# ESP32_Alarm.net
KiCad netlist of a schematic drawn in EAGLE
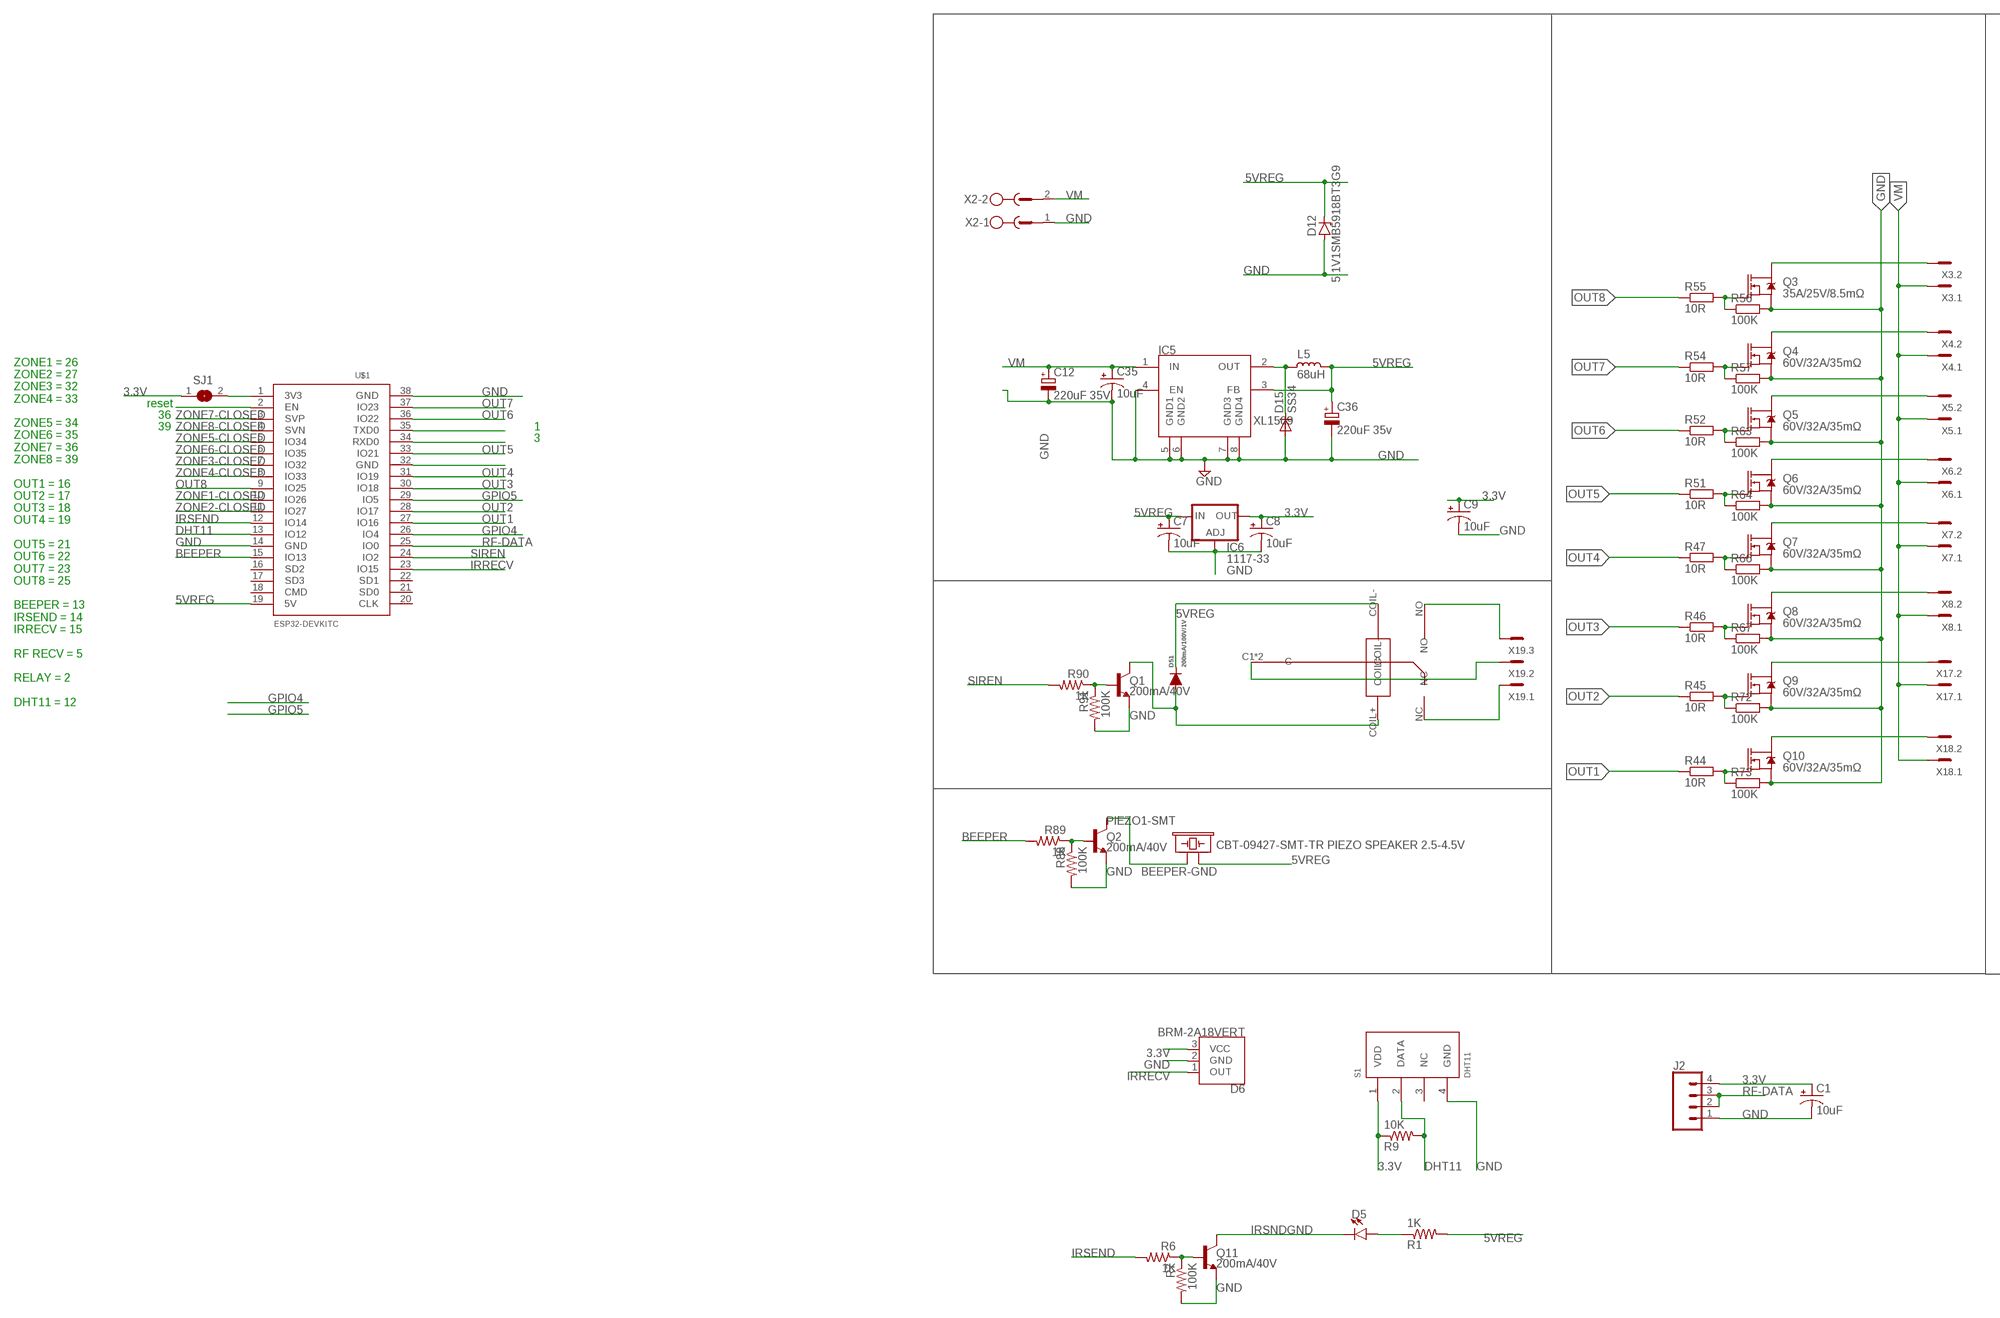
[diagram p0: schematic, sheet 1, part 1 of 2]
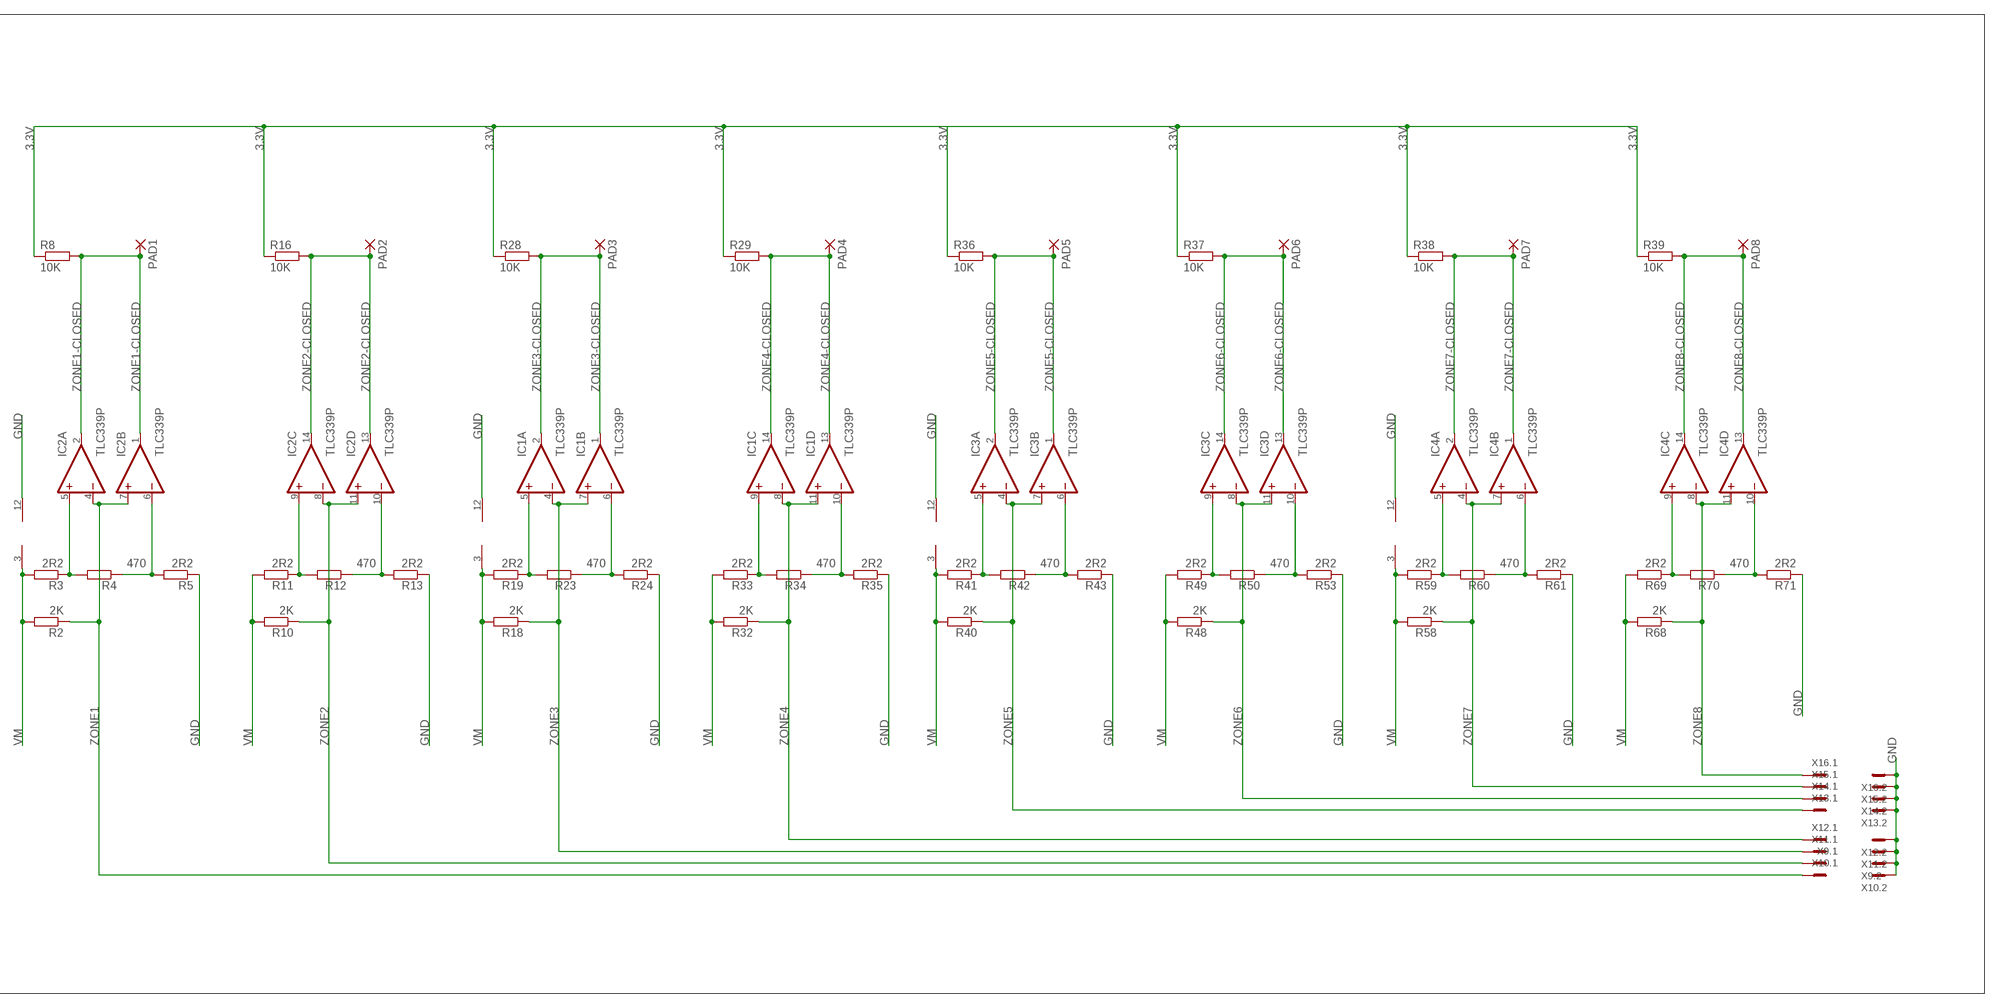
[diagram p1: schematic, sheet 1, part 2 of 2]

(export (version "E")
  (design (tool "Eeschema 10.0.6"))
  (components
    (comp (ref "C1")
      (value "10uF")
      (footprint "eagle-import:EIA3216")
      (libsource (lib "eagle-import") (part "CAP_POL1206"))
    )
    (comp (ref "C7")
      (value "10uF")
      (footprint "eagle-import:EIA3216")
      (libsource (lib "eagle-import") (part "CAP_POL1206"))
    )
    (comp (ref "C8")
      (value "10uF")
      (footprint "eagle-import:EIA3216")
      (libsource (lib "eagle-import") (part "CAP_POL1206"))
    )
    (comp (ref "C9")
      (value "10uF")
      (footprint "eagle-import:EIA3216")
      (libsource (lib "eagle-import") (part "CAP_POL1206"))
    )
    (comp (ref "C12")
      (value "220uF 35V")
      (footprint "eagle-import:E3,5-8")
      (libsource (lib "eagle-import") (part "CPOL-EUE3.5-8"))
    )
    (comp (ref "C35")
      (value "10uF")
      (footprint "eagle-import:EIA3216")
      (libsource (lib "eagle-import") (part "CAP_POL1206"))
    )
    (comp (ref "C36")
      (value "220uF 35v")
      (footprint "eagle-import:E3,5-8")
      (libsource (lib "eagle-import") (part "CPOL-EUE3.5-8"))
    )
    (comp (ref "D5")
      (value "LED3MM")
      (footprint "eagle-import:LED_3MM")
      (libsource (lib "eagle-import") (part "LED3MM"))
    )
    (comp (ref "D6")
      (value "BRM-2A18VERT")
      (footprint "eagle-import:BRM-2508_VERT")
      (libsource (lib "eagle-import") (part "BRM-2A18VERT"))
    )
    (comp (ref "D12")
      (value "5.1V1SMB5918BT3G9")
      (footprint "eagle-import:SMB")
      (libsource (lib "eagle-import") (part "ZENER-DIODESMB"))
    )
    (comp (ref "D15")
      (value "SS34")
      (footprint "eagle-import:DO-214AC")
      (libsource (lib "eagle-import") (part "DIODE-DO-214AC"))
    )
    (comp (ref "D51")
      (value "200mA/100V/1V")
      (footprint "eagle-import:DIODE-1N4148-KIT")
      (libsource (lib "eagle-import") (part "DIODE-KIT"))
    )
    (comp (ref "IC1")
      (value "TLC339P")
      (footprint "eagle-import:DIL14")
      (libsource (lib "eagle-import") (part "TLC339P"))
    )
    (comp (ref "IC2")
      (value "TLC339P")
      (footprint "eagle-import:DIL14")
      (libsource (lib "eagle-import") (part "TLC339P"))
    )
    (comp (ref "IC3")
      (value "TLC339P")
      (footprint "eagle-import:DIL14")
      (libsource (lib "eagle-import") (part "TLC339P"))
    )
    (comp (ref "IC4")
      (value "TLC339P")
      (footprint "eagle-import:DIL14")
      (libsource (lib "eagle-import") (part "TLC339P"))
    )
    (comp (ref "IC5")
      (value "XL1509")
      (footprint "eagle-import:SO08")
      (libsource (lib "eagle-import") (part "XL1509"))
    )
    (comp (ref "IC6")
      (value "1117-33")
      (footprint "eagle-import:SOT223")
      (libsource (lib "eagle-import") (part "LD117A?S33TR"))
    )
    (comp (ref "J1")
      (value "JRC-21F-4100")
      (footprint "eagle-import:JRC-21F-4100")
      (libsource (lib "eagle-import") (part "JRC-21F-4100"))
    )
    (comp (ref "J2")
      (value "CONN_04LOCK")
      (footprint "eagle-import:1X04_LOCK")
      (libsource (lib "eagle-import") (part "CONN_04LOCK"))
    )
    (comp (ref "L5")
      (value "68uH")
      (footprint "eagle-import:CD75")
      (libsource (lib "eagle-import") (part "L_CD75"))
    )
    (comp (ref "PAD1")
      (value "2,15/1,0")
      (footprint "eagle-import:2,15_1,0")
      (libsource (lib "eagle-import") (part "2,15/1,0"))
    )
    (comp (ref "PAD2")
      (value "2,15/1,0")
      (footprint "eagle-import:2,15_1,0")
      (libsource (lib "eagle-import") (part "2,15/1,0"))
    )
    (comp (ref "PAD3")
      (value "2,15/1,0")
      (footprint "eagle-import:2,15_1,0")
      (libsource (lib "eagle-import") (part "2,15/1,0"))
    )
    (comp (ref "PAD4")
      (value "2,15/1,0")
      (footprint "eagle-import:2,15_1,0")
      (libsource (lib "eagle-import") (part "2,15/1,0"))
    )
    (comp (ref "PAD5")
      (value "2,15/1,0")
      (footprint "eagle-import:2,15_1,0")
      (libsource (lib "eagle-import") (part "2,15/1,0"))
    )
    (comp (ref "PAD6")
      (value "2,15/1,0")
      (footprint "eagle-import:2,15_1,0")
      (libsource (lib "eagle-import") (part "2,15/1,0"))
    )
    (comp (ref "PAD7")
      (value "2,15/1,0")
      (footprint "eagle-import:2,15_1,0")
      (libsource (lib "eagle-import") (part "2,15/1,0"))
    )
    (comp (ref "PAD8")
      (value "2,15/1,0")
      (footprint "eagle-import:2,15_1,0")
      (libsource (lib "eagle-import") (part "2,15/1,0"))
    )
    (comp (ref "PIEZO1-SMT")
      (value "CBT-09427-SMT-TR PIEZO SPEAKER 2.5-4.5V")
      (footprint "eagle-import:BUZZER-12MM")
      (libsource (lib "eagle-import") (part "BUZZER-PTH"))
    )
    (comp (ref "Q1")
      (value "200mA/40V")
      (footprint "eagle-import:TO-92")
      (libsource (lib "eagle-import") (part "TRANS_NPN-2N3904"))
    )
    (comp (ref "Q2")
      (value "200mA/40V")
      (footprint "eagle-import:TO-92")
      (libsource (lib "eagle-import") (part "TRANS_NPN-2N3904"))
    )
    (comp (ref "Q3")
      (value "35A/25V/8.5mΩ")
      (footprint "eagle-import:DPAK")
      (libsource (lib "eagle-import") (part "MOSFET-NCH-FDD8780"))
    )
    (comp (ref "Q4")
      (value "60V/32A/35mΩ")
      (footprint "eagle-import:TO220V")
      (libsource (lib "eagle-import") (part "MOSFET-NCH-FQP30N06L"))
    )
    (comp (ref "Q5")
      (value "60V/32A/35mΩ")
      (footprint "eagle-import:TO220V")
      (libsource (lib "eagle-import") (part "MOSFET-NCH-FQP30N06L"))
    )
    (comp (ref "Q6")
      (value "60V/32A/35mΩ")
      (footprint "eagle-import:TO220V")
      (libsource (lib "eagle-import") (part "MOSFET-NCH-FQP30N06L"))
    )
    (comp (ref "Q7")
      (value "60V/32A/35mΩ")
      (footprint "eagle-import:TO220V")
      (libsource (lib "eagle-import") (part "MOSFET-NCH-FQP30N06L"))
    )
    (comp (ref "Q8")
      (value "60V/32A/35mΩ")
      (footprint "eagle-import:TO220V")
      (libsource (lib "eagle-import") (part "MOSFET-NCH-FQP30N06L"))
    )
    (comp (ref "Q9")
      (value "60V/32A/35mΩ")
      (footprint "eagle-import:TO220V")
      (libsource (lib "eagle-import") (part "MOSFET-NCH-FQP30N06L"))
    )
    (comp (ref "Q10")
      (value "60V/32A/35mΩ")
      (footprint "eagle-import:TO220V")
      (libsource (lib "eagle-import") (part "MOSFET-NCH-FQP30N06L"))
    )
    (comp (ref "Q11")
      (value "200mA/40V")
      (footprint "eagle-import:TO-92")
      (libsource (lib "eagle-import") (part "TRANS_NPN-2N3904"))
    )
    (comp (ref "R1")
      (value "1K")
      (footprint "eagle-import:0204_7")
      (libsource (lib "eagle-import") (part "R-US_0204/7"))
    )
    (comp (ref "R2")
      (value "2K")
      (footprint "eagle-import:0204_7")
      (libsource (lib "eagle-import") (part "R-EU_0204/7"))
    )
    (comp (ref "R3")
      (value "2R2")
      (footprint "eagle-import:0204_7")
      (libsource (lib "eagle-import") (part "R-EU_0204/7"))
    )
    (comp (ref "R4")
      (value "470")
      (footprint "eagle-import:0204_7")
      (libsource (lib "eagle-import") (part "R-EU_0204/7"))
    )
    (comp (ref "R5")
      (value "2R2")
      (footprint "eagle-import:0204_7")
      (libsource (lib "eagle-import") (part "R-EU_0204/7"))
    )
    (comp (ref "R6")
      (value "1K")
      (footprint "eagle-import:0204_7")
      (libsource (lib "eagle-import") (part "adafruit_420_R-US_0204/7"))
    )
    (comp (ref "R7")
      (value "100K")
      (footprint "eagle-import:0204_7")
      (libsource (lib "eagle-import") (part "adafruit_420_R-US_0204/7"))
    )
    (comp (ref "R8")
      (value "10K")
      (footprint "eagle-import:0204_7")
      (libsource (lib "eagle-import") (part "R-EU_0204/7"))
    )
    (comp (ref "R9")
      (value "10K")
      (footprint "eagle-import:0204_7")
      (libsource (lib "eagle-import") (part "R-US_0204/7"))
    )
    (comp (ref "R10")
      (value "2K")
      (footprint "eagle-import:0204_7")
      (libsource (lib "eagle-import") (part "R-EU_0204/7"))
    )
    (comp (ref "R11")
      (value "2R2")
      (footprint "eagle-import:0204_7")
      (libsource (lib "eagle-import") (part "R-EU_0204/7"))
    )
    (comp (ref "R12")
      (value "470")
      (footprint "eagle-import:0204_7")
      (libsource (lib "eagle-import") (part "R-EU_0204/7"))
    )
    (comp (ref "R13")
      (value "2R2")
      (footprint "eagle-import:0204_7")
      (libsource (lib "eagle-import") (part "R-EU_0204/7"))
    )
    (comp (ref "R16")
      (value "10K")
      (footprint "eagle-import:0204_7")
      (libsource (lib "eagle-import") (part "R-EU_0204/7"))
    )
    (comp (ref "R18")
      (value "2K")
      (footprint "eagle-import:0204_7")
      (libsource (lib "eagle-import") (part "R-EU_0204/7"))
    )
    (comp (ref "R19")
      (value "2R2")
      (footprint "eagle-import:0204_7")
      (libsource (lib "eagle-import") (part "R-EU_0204/7"))
    )
    (comp (ref "R23")
      (value "470")
      (footprint "eagle-import:0204_7")
      (libsource (lib "eagle-import") (part "R-EU_0204/7"))
    )
    (comp (ref "R24")
      (value "2R2")
      (footprint "eagle-import:0204_7")
      (libsource (lib "eagle-import") (part "R-EU_0204/7"))
    )
    (comp (ref "R28")
      (value "10K")
      (footprint "eagle-import:0204_7")
      (libsource (lib "eagle-import") (part "R-EU_0204/7"))
    )
    (comp (ref "R29")
      (value "10K")
      (footprint "eagle-import:0204_7")
      (libsource (lib "eagle-import") (part "R-EU_0204/7"))
    )
    (comp (ref "R32")
      (value "2K")
      (footprint "eagle-import:0204_7")
      (libsource (lib "eagle-import") (part "R-EU_0204/7"))
    )
    (comp (ref "R33")
      (value "2R2")
      (footprint "eagle-import:0204_7")
      (libsource (lib "eagle-import") (part "R-EU_0204/7"))
    )
    (comp (ref "R34")
      (value "470")
      (footprint "eagle-import:0204_7")
      (libsource (lib "eagle-import") (part "R-EU_0204/7"))
    )
    (comp (ref "R35")
      (value "2R2")
      (footprint "eagle-import:0204_7")
      (libsource (lib "eagle-import") (part "R-EU_0204/7"))
    )
    (comp (ref "R36")
      (value "10K")
      (footprint "eagle-import:0204_7")
      (libsource (lib "eagle-import") (part "R-EU_0204/7"))
    )
    (comp (ref "R37")
      (value "10K")
      (footprint "eagle-import:0204_7")
      (libsource (lib "eagle-import") (part "R-EU_0204/7"))
    )
    (comp (ref "R38")
      (value "10K")
      (footprint "eagle-import:0204_7")
      (libsource (lib "eagle-import") (part "R-EU_0204/7"))
    )
    (comp (ref "R39")
      (value "10K")
      (footprint "eagle-import:0204_7")
      (libsource (lib "eagle-import") (part "R-EU_0204/7"))
    )
    (comp (ref "R40")
      (value "2K")
      (footprint "eagle-import:0204_7")
      (libsource (lib "eagle-import") (part "R-EU_0204/7"))
    )
    (comp (ref "R41")
      (value "2R2")
      (footprint "eagle-import:0204_7")
      (libsource (lib "eagle-import") (part "R-EU_0204/7"))
    )
    (comp (ref "R42")
      (value "470")
      (footprint "eagle-import:0204_7")
      (libsource (lib "eagle-import") (part "R-EU_0204/7"))
    )
    (comp (ref "R43")
      (value "2R2")
      (footprint "eagle-import:0204_7")
      (libsource (lib "eagle-import") (part "R-EU_0204/7"))
    )
    (comp (ref "R44")
      (value "10R")
      (footprint "eagle-import:0204_7")
      (libsource (lib "eagle-import") (part "R-EU_0204/7"))
    )
    (comp (ref "R45")
      (value "10R")
      (footprint "eagle-import:0204_7")
      (libsource (lib "eagle-import") (part "R-EU_0204/7"))
    )
    (comp (ref "R46")
      (value "10R")
      (footprint "eagle-import:0204_7")
      (libsource (lib "eagle-import") (part "R-EU_0204/7"))
    )
    (comp (ref "R47")
      (value "10R")
      (footprint "eagle-import:0204_7")
      (libsource (lib "eagle-import") (part "R-EU_0204/7"))
    )
    (comp (ref "R48")
      (value "2K")
      (footprint "eagle-import:0204_7")
      (libsource (lib "eagle-import") (part "R-EU_0204/7"))
    )
    (comp (ref "R49")
      (value "2R2")
      (footprint "eagle-import:0204_7")
      (libsource (lib "eagle-import") (part "R-EU_0204/7"))
    )
    (comp (ref "R50")
      (value "470")
      (footprint "eagle-import:0204_7")
      (libsource (lib "eagle-import") (part "R-EU_0204/7"))
    )
    (comp (ref "R51")
      (value "10R")
      (footprint "eagle-import:0204_7")
      (libsource (lib "eagle-import") (part "R-EU_0204/7"))
    )
    (comp (ref "R52")
      (value "10R")
      (footprint "eagle-import:0204_7")
      (libsource (lib "eagle-import") (part "R-EU_0204/7"))
    )
    (comp (ref "R53")
      (value "2R2")
      (footprint "eagle-import:0204_7")
      (libsource (lib "eagle-import") (part "R-EU_0204/7"))
    )
    (comp (ref "R54")
      (value "10R")
      (footprint "eagle-import:0204_7")
      (libsource (lib "eagle-import") (part "R-EU_0204/7"))
    )
    (comp (ref "R55")
      (value "10R")
      (footprint "eagle-import:0204_7")
      (libsource (lib "eagle-import") (part "R-EU_0204/7"))
    )
    (comp (ref "R56")
      (value "100K")
      (footprint "eagle-import:0204_7")
      (libsource (lib "eagle-import") (part "R-EU_0204/7"))
    )
    (comp (ref "R57")
      (value "100K")
      (footprint "eagle-import:0204_7")
      (libsource (lib "eagle-import") (part "R-EU_0204/7"))
    )
    (comp (ref "R58")
      (value "2K")
      (footprint "eagle-import:0204_7")
      (libsource (lib "eagle-import") (part "R-EU_0204/7"))
    )
    (comp (ref "R59")
      (value "2R2")
      (footprint "eagle-import:0204_7")
      (libsource (lib "eagle-import") (part "R-EU_0204/7"))
    )
    (comp (ref "R60")
      (value "470")
      (footprint "eagle-import:0204_7")
      (libsource (lib "eagle-import") (part "R-EU_0204/7"))
    )
    (comp (ref "R61")
      (value "2R2")
      (footprint "eagle-import:0204_7")
      (libsource (lib "eagle-import") (part "R-EU_0204/7"))
    )
    (comp (ref "R63")
      (value "100K")
      (footprint "eagle-import:0204_7")
      (libsource (lib "eagle-import") (part "R-EU_0204/7"))
    )
    (comp (ref "R64")
      (value "100K")
      (footprint "eagle-import:0204_7")
      (libsource (lib "eagle-import") (part "R-EU_0204/7"))
    )
    (comp (ref "R66")
      (value "100K")
      (footprint "eagle-import:0204_7")
      (libsource (lib "eagle-import") (part "R-EU_0204/7"))
    )
    (comp (ref "R67")
      (value "100K")
      (footprint "eagle-import:0204_7")
      (libsource (lib "eagle-import") (part "R-EU_0204/7"))
    )
    (comp (ref "R68")
      (value "2K")
      (footprint "eagle-import:0204_7")
      (libsource (lib "eagle-import") (part "R-EU_0204/7"))
    )
    (comp (ref "R69")
      (value "2R2")
      (footprint "eagle-import:0204_7")
      (libsource (lib "eagle-import") (part "R-EU_0204/7"))
    )
    (comp (ref "R70")
      (value "470")
      (footprint "eagle-import:0204_7")
      (libsource (lib "eagle-import") (part "R-EU_0204/7"))
    )
    (comp (ref "R71")
      (value "2R2")
      (footprint "eagle-import:0204_7")
      (libsource (lib "eagle-import") (part "R-EU_0204/7"))
    )
    (comp (ref "R72")
      (value "100K")
      (footprint "eagle-import:0204_7")
      (libsource (lib "eagle-import") (part "R-EU_0204/7"))
    )
    (comp (ref "R73")
      (value "100K")
      (footprint "eagle-import:0204_7")
      (libsource (lib "eagle-import") (part "R-EU_0204/7"))
    )
    (comp (ref "R88")
      (value "100K")
      (footprint "eagle-import:0204_7")
      (libsource (lib "eagle-import") (part "adafruit_420_R-US_0204/7"))
    )
    (comp (ref "R89")
      (value "1K")
      (footprint "eagle-import:0204_7")
      (libsource (lib "eagle-import") (part "adafruit_420_R-US_0204/7"))
    )
    (comp (ref "R90")
      (value "1K")
      (footprint "eagle-import:0204_7")
      (libsource (lib "eagle-import") (part "adafruit_420_R-US_0204/7"))
    )
    (comp (ref "R91")
      (value "100K")
      (footprint "eagle-import:0204_7")
      (libsource (lib "eagle-import") (part "adafruit_420_R-US_0204/7"))
    )
    (comp (ref "S1")
      (value "DHT11")
      (footprint "eagle-import:DHT11")
      (libsource (lib "eagle-import") (part "DHT11"))
    )
    (comp (ref "SJ1") (value "SJ") (footprint "eagle-import:SJ") (libsource (lib "eagle-import") (part "SJ")))
    (comp (ref "U$1")
      (value "ESP32DEVKITC")
      (footprint "eagle-import:ESP32-DEVKITC")
      (libsource (lib "eagle-import") (part "ESP32DEVKITC"))
    )
    (comp (ref "X2")
      (value "MSTBV2")
      (footprint "eagle-import:MSTBV2")
      (libsource (lib "eagle-import") (part "MSTBV2"))
    )
    (comp (ref "X3")
      (value "MCV2")
      (footprint "eagle-import:MCV2")
      (libsource (lib "eagle-import") (part "MCV2"))
    )
    (comp (ref "X4")
      (value "MCV2")
      (footprint "eagle-import:MCV2")
      (libsource (lib "eagle-import") (part "MCV2"))
    )
    (comp (ref "X5")
      (value "MCV2")
      (footprint "eagle-import:MCV2")
      (libsource (lib "eagle-import") (part "MCV2"))
    )
    (comp (ref "X6")
      (value "MCV2")
      (footprint "eagle-import:MCV2")
      (libsource (lib "eagle-import") (part "MCV2"))
    )
    (comp (ref "X7")
      (value "MCV2")
      (footprint "eagle-import:MCV2")
      (libsource (lib "eagle-import") (part "MCV2"))
    )
    (comp (ref "X8")
      (value "MCV2")
      (footprint "eagle-import:MCV2")
      (libsource (lib "eagle-import") (part "MCV2"))
    )
    (comp (ref "X9")
      (value "MCV2")
      (footprint "eagle-import:MCV2")
      (libsource (lib "eagle-import") (part "MCV2"))
    )
    (comp (ref "X10")
      (value "MCV2")
      (footprint "eagle-import:MCV2")
      (libsource (lib "eagle-import") (part "MCV2"))
    )
    (comp (ref "X11")
      (value "MCV2")
      (footprint "eagle-import:MCV2")
      (libsource (lib "eagle-import") (part "MCV2"))
    )
    (comp (ref "X12")
      (value "MCV2")
      (footprint "eagle-import:MCV2")
      (libsource (lib "eagle-import") (part "MCV2"))
    )
    (comp (ref "X13")
      (value "MCV2")
      (footprint "eagle-import:MCV2")
      (libsource (lib "eagle-import") (part "MCV2"))
    )
    (comp (ref "X14")
      (value "MCV2")
      (footprint "eagle-import:MCV2")
      (libsource (lib "eagle-import") (part "MCV2"))
    )
    (comp (ref "X15")
      (value "MCV2")
      (footprint "eagle-import:MCV2")
      (libsource (lib "eagle-import") (part "MCV2"))
    )
    (comp (ref "X16")
      (value "MCV2")
      (footprint "eagle-import:MCV2")
      (libsource (lib "eagle-import") (part "MCV2"))
    )
    (comp (ref "X17")
      (value "MCV2")
      (footprint "eagle-import:MCV2")
      (libsource (lib "eagle-import") (part "MCV2"))
    )
    (comp (ref "X18")
      (value "MCV2")
      (footprint "eagle-import:MCV2")
      (libsource (lib "eagle-import") (part "MCV2"))
    )
    (comp (ref "X19")
      (value "MCV3")
      (footprint "eagle-import:MCV3")
      (libsource (lib "eagle-import") (part "MCV3"))
    )
  )
  (nets
    (net (code "1") (name "/3.3V") (class "Default")
      (node (ref "C1") (pin "A") (pinfunction "+_A") (pintype "passive"))
      (node (ref "C8") (pin "A") (pinfunction "+_A") (pintype "passive"))
      (node (ref "C9") (pin "A") (pinfunction "+_A") (pintype "passive"))
      (node (ref "D6") (pin "3") (pinfunction "VCC_3") (pintype "bidirectional"))
      (node (ref "IC6") (pin "4") (pinfunction "OUT_4") (pintype "passive"))
      (node (ref "J2") (pin "4") (pinfunction "4_4") (pintype "passive"))
      (node (ref "R16") (pin "1") (pinfunction "1_1") (pintype "passive"))
      (node (ref "R28") (pin "1") (pinfunction "1_1") (pintype "passive"))
      (node (ref "R29") (pin "1") (pinfunction "1_1") (pintype "passive"))
      (node (ref "R36") (pin "1") (pinfunction "1_1") (pintype "passive"))
      (node (ref "R37") (pin "1") (pinfunction "1_1") (pintype "passive"))
      (node (ref "R38") (pin "1") (pinfunction "1_1") (pintype "passive"))
      (node (ref "R39") (pin "1") (pinfunction "1_1") (pintype "passive"))
      (node (ref "R8") (pin "1") (pinfunction "1_1") (pintype "passive"))
      (node (ref "R9") (pin "1") (pinfunction "1_1") (pintype "passive"))
      (node (ref "S1") (pin "1") (pinfunction "VDD_1") (pintype "power_in"))
      (node (ref "SJ1") (pin "1") (pinfunction "1_1") (pintype "passive"))
    )
    (net (code "2") (name "/5VREG") (class "Default")
      (node (ref "C36") (pin "+") (pinfunction "+_+") (pintype "passive"))
      (node (ref "C7") (pin "A") (pinfunction "+_A") (pintype "passive"))
      (node (ref "D12") (pin "C") (pinfunction "C_C") (pintype "passive"))
      (node (ref "D51") (pin "C") (pinfunction "C_C") (pintype "passive"))
      (node (ref "IC5") (pin "3") (pinfunction "FB_3") (pintype "bidirectional"))
      (node (ref "IC6") (pin "3") (pinfunction "IN_3") (pintype "input"))
      (node (ref "J1") (pin "COIL-") (pinfunction "COIL-_COIL-") (pintype "bidirectional"))
      (node (ref "L5") (pin "1") (pinfunction "1_1") (pintype "passive"))
      (node (ref "PIEZO1-SMT") (pin "+") (pinfunction "1_+") (pintype "passive"))
      (node (ref "R1") (pin "2") (pinfunction "2_2") (pintype "passive"))
      (node (ref "U$1") (pin "19") (pinfunction "5V_19") (pintype "bidirectional"))
    )
    (net (code "3") (name "/BEEPER") (class "Default")
      (node (ref "R89") (pin "2") (pinfunction "2_2") (pintype "passive"))
      (node (ref "U$1") (pin "15") (pinfunction "IO13_15") (pintype "bidirectional"))
    )
    (net (code "4") (name "/BEEPER-GND") (class "Default")
      (node (ref "PIEZO1-SMT") (pin "-") (pinfunction "2_-") (pintype "passive"))
      (node (ref "Q2") (pin "3") (pinfunction "C_3") (pintype "passive"))
    )
    (net (code "5") (name "/DHT11") (class "Default")
      (node (ref "R9") (pin "2") (pinfunction "2_2") (pintype "passive"))
      (node (ref "S1") (pin "2") (pinfunction "DATA_2") (pintype "bidirectional"))
      (node (ref "U$1") (pin "13") (pinfunction "IO12_13") (pintype "bidirectional"))
    )
    (net (code "6") (name "/GPIO4") (class "Default")
      (node (ref "U$1") (pin "26") (pinfunction "IO4_26") (pintype "bidirectional"))
    )
    (net (code "7") (name "/GPIO5") (class "Default")
      (node (ref "U$1") (pin "29") (pinfunction "IO5_29") (pintype "bidirectional"))
    )
    (net (code "8") (name "/IRRECV") (class "Default")
      (node (ref "D6") (pin "1") (pinfunction "OUT_1") (pintype "bidirectional"))
      (node (ref "U$1") (pin "23") (pinfunction "IO15_23") (pintype "bidirectional"))
    )
    (net (code "9") (name "/IRSEND") (class "Default")
      (node (ref "R6") (pin "2") (pinfunction "2_2") (pintype "passive"))
      (node (ref "U$1") (pin "12") (pinfunction "IO14_12") (pintype "bidirectional"))
    )
    (net (code "10") (name "/IRSNDGND") (class "Default")
      (node (ref "D5") (pin "K") (pinfunction "C_K") (pintype "passive"))
      (node (ref "Q11") (pin "3") (pinfunction "C_3") (pintype "passive"))
    )
    (net (code "11") (name "/RF-DATA") (class "Default")
      (node (ref "J2") (pin "2") (pinfunction "2_2") (pintype "passive"))
      (node (ref "J2") (pin "3") (pinfunction "3_3") (pintype "passive"))
      (node (ref "U$1") (pin "25") (pinfunction "IO0_25") (pintype "bidirectional"))
    )
    (net (code "12") (name "/SIREN") (class "Default")
      (node (ref "R90") (pin "2") (pinfunction "2_2") (pintype "passive"))
      (node (ref "U$1") (pin "24") (pinfunction "IO2_24") (pintype "bidirectional"))
    )
    (net (code "13") (name "/ZONE1") (class "Default")
      (node (ref "IC2") (pin "4") (pinfunction "-IN_4") (pintype "input"))
      (node (ref "IC2") (pin "7") (pinfunction "+IN_7") (pintype "input"))
      (node (ref "R2") (pin "1") (pinfunction "1_1") (pintype "passive"))
      (node (ref "X10") (pin "1") (pinfunction "SK_1") (pintype "passive"))
    )
    (net (code "14") (name "/ZONE1-CLOSED") (class "Default")
      (node (ref "IC2") (pin "1") (pinfunction "OUT_1") (pintype "output"))
      (node (ref "IC2") (pin "2") (pinfunction "OUT_2") (pintype "output"))
      (node (ref "PAD1") (pin "1") (pinfunction "P_1") (pintype "passive"))
      (node (ref "R8") (pin "2") (pinfunction "2_2") (pintype "passive"))
      (node (ref "U$1") (pin "10") (pinfunction "IO26_10") (pintype "bidirectional"))
    )
    (net (code "15") (name "/ZONE2") (class "Default")
      (node (ref "IC2") (pin "11") (pinfunction "+IN_11") (pintype "input"))
      (node (ref "IC2") (pin "8") (pinfunction "-IN_8") (pintype "input"))
      (node (ref "R10") (pin "1") (pinfunction "1_1") (pintype "passive"))
      (node (ref "X9") (pin "1") (pinfunction "SK_1") (pintype "passive"))
    )
    (net (code "16") (name "/ZONE2-CLOSED") (class "Default")
      (node (ref "IC2") (pin "13") (pinfunction "OUT_13") (pintype "output"))
      (node (ref "IC2") (pin "14") (pinfunction "OUT_14") (pintype "output"))
      (node (ref "PAD2") (pin "1") (pinfunction "P_1") (pintype "passive"))
      (node (ref "R16") (pin "2") (pinfunction "2_2") (pintype "passive"))
      (node (ref "U$1") (pin "11") (pinfunction "IO27_11") (pintype "bidirectional"))
    )
    (net (code "17") (name "/ZONE3") (class "Default")
      (node (ref "IC1") (pin "4") (pinfunction "-IN_4") (pintype "input"))
      (node (ref "IC1") (pin "7") (pinfunction "+IN_7") (pintype "input"))
      (node (ref "R18") (pin "1") (pinfunction "1_1") (pintype "passive"))
      (node (ref "X11") (pin "1") (pinfunction "SK_1") (pintype "passive"))
    )
    (net (code "18") (name "/ZONE3-CLOSED") (class "Default")
      (node (ref "IC1") (pin "1") (pinfunction "OUT_1") (pintype "output"))
      (node (ref "IC1") (pin "2") (pinfunction "OUT_2") (pintype "output"))
      (node (ref "PAD3") (pin "1") (pinfunction "P_1") (pintype "passive"))
      (node (ref "R28") (pin "2") (pinfunction "2_2") (pintype "passive"))
      (node (ref "U$1") (pin "7") (pinfunction "IO32_7") (pintype "bidirectional"))
    )
    (net (code "19") (name "/ZONE4") (class "Default")
      (node (ref "IC1") (pin "11") (pinfunction "+IN_11") (pintype "input"))
      (node (ref "IC1") (pin "8") (pinfunction "-IN_8") (pintype "input"))
      (node (ref "R32") (pin "1") (pinfunction "1_1") (pintype "passive"))
      (node (ref "X12") (pin "1") (pinfunction "SK_1") (pintype "passive"))
    )
    (net (code "20") (name "/ZONE4-CLOSED") (class "Default")
      (node (ref "IC1") (pin "13") (pinfunction "OUT_13") (pintype "output"))
      (node (ref "IC1") (pin "14") (pinfunction "OUT_14") (pintype "output"))
      (node (ref "PAD4") (pin "1") (pinfunction "P_1") (pintype "passive"))
      (node (ref "R29") (pin "2") (pinfunction "2_2") (pintype "passive"))
      (node (ref "U$1") (pin "8") (pinfunction "IO33_8") (pintype "bidirectional"))
    )
    (net (code "21") (name "/ZONE5") (class "Default")
      (node (ref "IC3") (pin "4") (pinfunction "-IN_4") (pintype "input"))
      (node (ref "IC3") (pin "7") (pinfunction "+IN_7") (pintype "input"))
      (node (ref "R40") (pin "1") (pinfunction "1_1") (pintype "passive"))
      (node (ref "X13") (pin "1") (pinfunction "SK_1") (pintype "passive"))
    )
    (net (code "22") (name "/ZONE5-CLOSED") (class "Default")
      (node (ref "IC3") (pin "1") (pinfunction "OUT_1") (pintype "output"))
      (node (ref "IC3") (pin "2") (pinfunction "OUT_2") (pintype "output"))
      (node (ref "PAD5") (pin "1") (pinfunction "P_1") (pintype "passive"))
      (node (ref "R36") (pin "2") (pinfunction "2_2") (pintype "passive"))
      (node (ref "U$1") (pin "5") (pinfunction "IO34_5") (pintype "bidirectional"))
    )
    (net (code "23") (name "/ZONE6") (class "Default")
      (node (ref "IC3") (pin "11") (pinfunction "+IN_11") (pintype "input"))
      (node (ref "IC3") (pin "8") (pinfunction "-IN_8") (pintype "input"))
      (node (ref "R48") (pin "1") (pinfunction "1_1") (pintype "passive"))
      (node (ref "X14") (pin "1") (pinfunction "SK_1") (pintype "passive"))
    )
    (net (code "24") (name "/ZONE6-CLOSED") (class "Default")
      (node (ref "IC3") (pin "13") (pinfunction "OUT_13") (pintype "output"))
      (node (ref "IC3") (pin "14") (pinfunction "OUT_14") (pintype "output"))
      (node (ref "PAD6") (pin "1") (pinfunction "P_1") (pintype "passive"))
      (node (ref "R37") (pin "2") (pinfunction "2_2") (pintype "passive"))
      (node (ref "U$1") (pin "6") (pinfunction "IO35_6") (pintype "bidirectional"))
    )
    (net (code "25") (name "/ZONE7") (class "Default")
      (node (ref "IC4") (pin "4") (pinfunction "-IN_4") (pintype "input"))
      (node (ref "IC4") (pin "7") (pinfunction "+IN_7") (pintype "input"))
      (node (ref "R58") (pin "1") (pinfunction "1_1") (pintype "passive"))
      (node (ref "X15") (pin "1") (pinfunction "SK_1") (pintype "passive"))
    )
    (net (code "26") (name "/ZONE7-CLOSED") (class "Default")
      (node (ref "IC4") (pin "1") (pinfunction "OUT_1") (pintype "output"))
      (node (ref "IC4") (pin "2") (pinfunction "OUT_2") (pintype "output"))
      (node (ref "PAD7") (pin "1") (pinfunction "P_1") (pintype "passive"))
      (node (ref "R38") (pin "2") (pinfunction "2_2") (pintype "passive"))
      (node (ref "U$1") (pin "3") (pinfunction "SVP_3") (pintype "bidirectional"))
    )
    (net (code "27") (name "/ZONE8") (class "Default")
      (node (ref "IC4") (pin "11") (pinfunction "+IN_11") (pintype "input"))
      (node (ref "IC4") (pin "8") (pinfunction "-IN_8") (pintype "input"))
      (node (ref "R68") (pin "1") (pinfunction "1_1") (pintype "passive"))
      (node (ref "X16") (pin "1") (pinfunction "SK_1") (pintype "passive"))
    )
    (net (code "28") (name "/ZONE8-CLOSED") (class "Default")
      (node (ref "IC4") (pin "13") (pinfunction "OUT_13") (pintype "output"))
      (node (ref "IC4") (pin "14") (pinfunction "OUT_14") (pintype "output"))
      (node (ref "PAD8") (pin "1") (pinfunction "P_1") (pintype "passive"))
      (node (ref "R39") (pin "2") (pinfunction "2_2") (pintype "passive"))
      (node (ref "U$1") (pin "4") (pinfunction "SVN_4") (pintype "bidirectional"))
    )
    (net (code "29") (name "GND") (class "Default")
      (node (ref "C1") (pin "C") (pinfunction "-_C") (pintype "passive"))
      (node (ref "C12") (pin "-") (pinfunction "-_-") (pintype "passive"))
      (node (ref "C35") (pin "C") (pinfunction "-_C") (pintype "passive"))
      (node (ref "C36") (pin "-") (pinfunction "-_-") (pintype "passive"))
      (node (ref "C7") (pin "C") (pinfunction "-_C") (pintype "passive"))
      (node (ref "C8") (pin "C") (pinfunction "-_C") (pintype "passive"))
      (node (ref "C9") (pin "C") (pinfunction "-_C") (pintype "passive"))
      (node (ref "D12") (pin "A") (pinfunction "A_A") (pintype "passive"))
      (node (ref "D15") (pin "2") (pinfunction "A_2") (pintype "passive"))
      (node (ref "D6") (pin "2") (pinfunction "GND_2") (pintype "bidirectional"))
      (node (ref "IC1") (pin "12") (pinfunction "V-_12") (pintype "power_in"))
      (node (ref "IC2") (pin "12") (pinfunction "V-_12") (pintype "power_in"))
      (node (ref "IC3") (pin "12") (pinfunction "V-_12") (pintype "power_in"))
      (node (ref "IC4") (pin "12") (pinfunction "V-_12") (pintype "power_in"))
      (node (ref "IC5") (pin "4") (pinfunction "EN_4") (pintype "bidirectional"))
      (node (ref "IC5") (pin "5") (pinfunction "GND1_5") (pintype "bidirectional"))
      (node (ref "IC5") (pin "6") (pinfunction "GND2_6") (pintype "bidirectional"))
      (node (ref "IC5") (pin "7") (pinfunction "GND3_7") (pintype "bidirectional"))
      (node (ref "IC5") (pin "8") (pinfunction "GND4_8") (pintype "bidirectional"))
      (node (ref "IC6") (pin "1") (pinfunction "ADJ_1") (pintype "input"))
      (node (ref "J2") (pin "1") (pinfunction "1_1") (pintype "passive"))
      (node (ref "Q1") (pin "1") (pinfunction "E_1") (pintype "passive"))
      (node (ref "Q10") (pin "3") (pinfunction "S_3") (pintype "bidirectional"))
      (node (ref "Q11") (pin "1") (pinfunction "E_1") (pintype "passive"))
      (node (ref "Q2") (pin "1") (pinfunction "E_1") (pintype "passive"))
      (node (ref "Q3") (pin "3") (pinfunction "S_3") (pintype "bidirectional"))
      (node (ref "Q4") (pin "3") (pinfunction "S_3") (pintype "bidirectional"))
      (node (ref "Q5") (pin "3") (pinfunction "S_3") (pintype "bidirectional"))
      (node (ref "Q6") (pin "3") (pinfunction "S_3") (pintype "bidirectional"))
      (node (ref "Q7") (pin "3") (pinfunction "S_3") (pintype "bidirectional"))
      (node (ref "Q8") (pin "3") (pinfunction "S_3") (pintype "bidirectional"))
      (node (ref "Q9") (pin "3") (pinfunction "S_3") (pintype "bidirectional"))
      (node (ref "R13") (pin "1") (pinfunction "1_1") (pintype "passive"))
      (node (ref "R24") (pin "1") (pinfunction "1_1") (pintype "passive"))
      (node (ref "R35") (pin "1") (pinfunction "1_1") (pintype "passive"))
      (node (ref "R43") (pin "1") (pinfunction "1_1") (pintype "passive"))
      (node (ref "R5") (pin "1") (pinfunction "1_1") (pintype "passive"))
      (node (ref "R53") (pin "1") (pinfunction "1_1") (pintype "passive"))
      (node (ref "R56") (pin "2") (pinfunction "2_2") (pintype "passive"))
      (node (ref "R57") (pin "2") (pinfunction "2_2") (pintype "passive"))
      (node (ref "R61") (pin "1") (pinfunction "1_1") (pintype "passive"))
      (node (ref "R63") (pin "2") (pinfunction "2_2") (pintype "passive"))
      (node (ref "R64") (pin "2") (pinfunction "2_2") (pintype "passive"))
      (node (ref "R66") (pin "2") (pinfunction "2_2") (pintype "passive"))
      (node (ref "R67") (pin "2") (pinfunction "2_2") (pintype "passive"))
      (node (ref "R7") (pin "2") (pinfunction "2_2") (pintype "passive"))
      (node (ref "R71") (pin "1") (pinfunction "1_1") (pintype "passive"))
      (node (ref "R72") (pin "2") (pinfunction "2_2") (pintype "passive"))
      (node (ref "R73") (pin "2") (pinfunction "2_2") (pintype "passive"))
      (node (ref "R88") (pin "2") (pinfunction "2_2") (pintype "passive"))
      (node (ref "R91") (pin "2") (pinfunction "2_2") (pintype "passive"))
      (node (ref "S1") (pin "4") (pinfunction "GND_4") (pintype "power_in"))
      (node (ref "U$1") (pin "14") (pinfunction "GND_14") (pintype "bidirectional"))
      (node (ref "U$1") (pin "38") (pinfunction "GND_38") (pintype "bidirectional"))
      (node (ref "X10") (pin "2") (pinfunction "SK_2") (pintype "passive"))
      (node (ref "X11") (pin "2") (pinfunction "SK_2") (pintype "passive"))
      (node (ref "X12") (pin "2") (pinfunction "SK_2") (pintype "passive"))
      (node (ref "X13") (pin "2") (pinfunction "SK_2") (pintype "passive"))
      (node (ref "X14") (pin "2") (pinfunction "SK_2") (pintype "passive"))
      (node (ref "X15") (pin "2") (pinfunction "SK_2") (pintype "passive"))
      (node (ref "X16") (pin "2") (pinfunction "SK_2") (pintype "passive"))
      (node (ref "X2") (pin "1") (pinfunction "SK_1") (pintype "passive"))
      (node (ref "X9") (pin "2") (pinfunction "SK_2") (pintype "passive"))
    )
    (net (code "30") (name "Net-(D5-PadA)") (class "Default")
      (node (ref "D5") (pin "A") (pinfunction "A_A") (pintype "passive"))
      (node (ref "R1") (pin "1") (pinfunction "1_1") (pintype "passive"))
    )
    (net (code "31") (name "Net-(D15-C)") (class "Default")
      (node (ref "D15") (pin "1") (pinfunction "C_1") (pintype "passive"))
      (node (ref "IC5") (pin "2") (pinfunction "OUT_2") (pintype "bidirectional"))
      (node (ref "L5") (pin "2") (pinfunction "2_2") (pintype "passive"))
    )
    (net (code "32") (name "Net-(IC1A-+IN)") (class "Default")
      (node (ref "IC1") (pin "5") (pinfunction "+IN_5") (pintype "input"))
      (node (ref "R19") (pin "1") (pinfunction "1_1") (pintype "passive"))
      (node (ref "R23") (pin "2") (pinfunction "2_2") (pintype "passive"))
    )
    (net (code "33") (name "Net-(IC1B--IN)") (class "Default")
      (node (ref "IC1") (pin "6") (pinfunction "-IN_6") (pintype "input"))
      (node (ref "R23") (pin "1") (pinfunction "1_1") (pintype "passive"))
      (node (ref "R24") (pin "2") (pinfunction "2_2") (pintype "passive"))
    )
    (net (code "34") (name "Net-(IC1C-+IN)") (class "Default")
      (node (ref "IC1") (pin "9") (pinfunction "+IN_9") (pintype "input"))
      (node (ref "R33") (pin "1") (pinfunction "1_1") (pintype "passive"))
      (node (ref "R34") (pin "2") (pinfunction "2_2") (pintype "passive"))
    )
    (net (code "35") (name "Net-(IC1D--IN)") (class "Default")
      (node (ref "IC1") (pin "10") (pinfunction "-IN_10") (pintype "input"))
      (node (ref "R34") (pin "1") (pinfunction "1_1") (pintype "passive"))
      (node (ref "R35") (pin "2") (pinfunction "2_2") (pintype "passive"))
    )
    (net (code "36") (name "Net-(IC2A-+IN)") (class "Default")
      (node (ref "IC2") (pin "5") (pinfunction "+IN_5") (pintype "input"))
      (node (ref "R3") (pin "1") (pinfunction "1_1") (pintype "passive"))
      (node (ref "R4") (pin "2") (pinfunction "2_2") (pintype "passive"))
    )
    (net (code "37") (name "Net-(IC2B--IN)") (class "Default")
      (node (ref "IC2") (pin "6") (pinfunction "-IN_6") (pintype "input"))
      (node (ref "R4") (pin "1") (pinfunction "1_1") (pintype "passive"))
      (node (ref "R5") (pin "2") (pinfunction "2_2") (pintype "passive"))
    )
    (net (code "38") (name "Net-(IC2C-+IN)") (class "Default")
      (node (ref "IC2") (pin "9") (pinfunction "+IN_9") (pintype "input"))
      (node (ref "R11") (pin "1") (pinfunction "1_1") (pintype "passive"))
      (node (ref "R12") (pin "2") (pinfunction "2_2") (pintype "passive"))
    )
    (net (code "39") (name "Net-(IC2D--IN)") (class "Default")
      (node (ref "IC2") (pin "10") (pinfunction "-IN_10") (pintype "input"))
      (node (ref "R12") (pin "1") (pinfunction "1_1") (pintype "passive"))
      (node (ref "R13") (pin "2") (pinfunction "2_2") (pintype "passive"))
    )
    (net (code "40") (name "Net-(IC3A-+IN)") (class "Default")
      (node (ref "IC3") (pin "5") (pinfunction "+IN_5") (pintype "input"))
      (node (ref "R41") (pin "1") (pinfunction "1_1") (pintype "passive"))
      (node (ref "R42") (pin "2") (pinfunction "2_2") (pintype "passive"))
    )
    (net (code "41") (name "Net-(IC3B--IN)") (class "Default")
      (node (ref "IC3") (pin "6") (pinfunction "-IN_6") (pintype "input"))
      (node (ref "R42") (pin "1") (pinfunction "1_1") (pintype "passive"))
      (node (ref "R43") (pin "2") (pinfunction "2_2") (pintype "passive"))
    )
    (net (code "42") (name "Net-(IC3C-+IN)") (class "Default")
      (node (ref "IC3") (pin "9") (pinfunction "+IN_9") (pintype "input"))
      (node (ref "R49") (pin "1") (pinfunction "1_1") (pintype "passive"))
      (node (ref "R50") (pin "2") (pinfunction "2_2") (pintype "passive"))
    )
    (net (code "43") (name "Net-(IC3D--IN)") (class "Default")
      (node (ref "IC3") (pin "10") (pinfunction "-IN_10") (pintype "input"))
      (node (ref "R50") (pin "1") (pinfunction "1_1") (pintype "passive"))
      (node (ref "R53") (pin "2") (pinfunction "2_2") (pintype "passive"))
    )
    (net (code "44") (name "Net-(IC4A-+IN)") (class "Default")
      (node (ref "IC4") (pin "5") (pinfunction "+IN_5") (pintype "input"))
      (node (ref "R59") (pin "1") (pinfunction "1_1") (pintype "passive"))
      (node (ref "R60") (pin "2") (pinfunction "2_2") (pintype "passive"))
    )
    (net (code "45") (name "Net-(IC4B--IN)") (class "Default")
      (node (ref "IC4") (pin "6") (pinfunction "-IN_6") (pintype "input"))
      (node (ref "R60") (pin "1") (pinfunction "1_1") (pintype "passive"))
      (node (ref "R61") (pin "2") (pinfunction "2_2") (pintype "passive"))
    )
    (net (code "46") (name "Net-(IC4C-+IN)") (class "Default")
      (node (ref "IC4") (pin "9") (pinfunction "+IN_9") (pintype "input"))
      (node (ref "R69") (pin "1") (pinfunction "1_1") (pintype "passive"))
      (node (ref "R70") (pin "2") (pinfunction "2_2") (pintype "passive"))
    )
    (net (code "47") (name "Net-(IC4D--IN)") (class "Default")
      (node (ref "IC4") (pin "10") (pinfunction "-IN_10") (pintype "input"))
      (node (ref "R70") (pin "1") (pinfunction "1_1") (pintype "passive"))
      (node (ref "R71") (pin "2") (pinfunction "2_2") (pintype "passive"))
    )
    (net (code "48") (name "Net-(J1-COIL=)") (class "Default")
      (node (ref "D51") (pin "A") (pinfunction "A_A") (pintype "passive"))
      (node (ref "J1") (pin "COIL+") (pinfunction "COIL=_COIL+") (pintype "bidirectional"))
      (node (ref "Q1") (pin "3") (pinfunction "C_3") (pintype "passive"))
    )
    (net (code "49") (name "Net-(Q1-B)") (class "Default")
      (node (ref "Q1") (pin "2") (pinfunction "B_2") (pintype "passive"))
      (node (ref "R90") (pin "1") (pinfunction "1_1") (pintype "passive"))
      (node (ref "R91") (pin "1") (pinfunction "1_1") (pintype "passive"))
    )
    (net (code "50") (name "Net-(Q2-B)") (class "Default")
      (node (ref "Q2") (pin "2") (pinfunction "B_2") (pintype "passive"))
      (node (ref "R88") (pin "1") (pinfunction "1_1") (pintype "passive"))
      (node (ref "R89") (pin "1") (pinfunction "1_1") (pintype "passive"))
    )
    (net (code "51") (name "Net-(Q3-D)") (class "Default")
      (node (ref "Q3") (pin "4") (pinfunction "D_4") (pintype "bidirectional"))
      (node (ref "X3") (pin "2") (pinfunction "SK_2") (pintype "passive"))
    )
    (net (code "52") (name "Net-(Q3-G)") (class "Default")
      (node (ref "Q3") (pin "1") (pinfunction "G_1") (pintype "bidirectional"))
      (node (ref "R55") (pin "2") (pinfunction "2_2") (pintype "passive"))
      (node (ref "R56") (pin "1") (pinfunction "1_1") (pintype "passive"))
    )
    (net (code "53") (name "Net-(Q4-D)") (class "Default")
      (node (ref "Q4") (pin "2") (pinfunction "D_2") (pintype "bidirectional"))
      (node (ref "X4") (pin "2") (pinfunction "SK_2") (pintype "passive"))
    )
    (net (code "54") (name "Net-(Q4-G)") (class "Default")
      (node (ref "Q4") (pin "1") (pinfunction "G_1") (pintype "bidirectional"))
      (node (ref "R54") (pin "2") (pinfunction "2_2") (pintype "passive"))
      (node (ref "R57") (pin "1") (pinfunction "1_1") (pintype "passive"))
    )
    (net (code "55") (name "Net-(Q5-D)") (class "Default")
      (node (ref "Q5") (pin "2") (pinfunction "D_2") (pintype "bidirectional"))
      (node (ref "X5") (pin "2") (pinfunction "SK_2") (pintype "passive"))
    )
    (net (code "56") (name "Net-(Q5-G)") (class "Default")
      (node (ref "Q5") (pin "1") (pinfunction "G_1") (pintype "bidirectional"))
      (node (ref "R52") (pin "2") (pinfunction "2_2") (pintype "passive"))
      (node (ref "R63") (pin "1") (pinfunction "1_1") (pintype "passive"))
    )
    (net (code "57") (name "Net-(Q6-D)") (class "Default")
      (node (ref "Q6") (pin "2") (pinfunction "D_2") (pintype "bidirectional"))
      (node (ref "X6") (pin "2") (pinfunction "SK_2") (pintype "passive"))
    )
    (net (code "58") (name "Net-(Q6-G)") (class "Default")
      (node (ref "Q6") (pin "1") (pinfunction "G_1") (pintype "bidirectional"))
      (node (ref "R51") (pin "2") (pinfunction "2_2") (pintype "passive"))
      (node (ref "R64") (pin "1") (pinfunction "1_1") (pintype "passive"))
    )
    (net (code "59") (name "Net-(Q7-D)") (class "Default")
      (node (ref "Q7") (pin "2") (pinfunction "D_2") (pintype "bidirectional"))
      (node (ref "X7") (pin "2") (pinfunction "SK_2") (pintype "passive"))
    )
    (net (code "60") (name "Net-(Q7-G)") (class "Default")
      (node (ref "Q7") (pin "1") (pinfunction "G_1") (pintype "bidirectional"))
      (node (ref "R47") (pin "2") (pinfunction "2_2") (pintype "passive"))
      (node (ref "R66") (pin "1") (pinfunction "1_1") (pintype "passive"))
    )
    (net (code "61") (name "Net-(Q8-D)") (class "Default")
      (node (ref "Q8") (pin "2") (pinfunction "D_2") (pintype "bidirectional"))
      (node (ref "X8") (pin "2") (pinfunction "SK_2") (pintype "passive"))
    )
    (net (code "62") (name "Net-(Q8-G)") (class "Default")
      (node (ref "Q8") (pin "1") (pinfunction "G_1") (pintype "bidirectional"))
      (node (ref "R46") (pin "2") (pinfunction "2_2") (pintype "passive"))
      (node (ref "R67") (pin "1") (pinfunction "1_1") (pintype "passive"))
    )
    (net (code "63") (name "Net-(Q9-D)") (class "Default")
      (node (ref "Q9") (pin "2") (pinfunction "D_2") (pintype "bidirectional"))
      (node (ref "X17") (pin "2") (pinfunction "SK_2") (pintype "passive"))
    )
    (net (code "64") (name "Net-(Q9-G)") (class "Default")
      (node (ref "Q9") (pin "1") (pinfunction "G_1") (pintype "bidirectional"))
      (node (ref "R45") (pin "2") (pinfunction "2_2") (pintype "passive"))
      (node (ref "R72") (pin "1") (pinfunction "1_1") (pintype "passive"))
    )
    (net (code "65") (name "Net-(Q10-D)") (class "Default")
      (node (ref "Q10") (pin "2") (pinfunction "D_2") (pintype "bidirectional"))
      (node (ref "X18") (pin "2") (pinfunction "SK_2") (pintype "passive"))
    )
    (net (code "66") (name "Net-(Q10-G)") (class "Default")
      (node (ref "Q10") (pin "1") (pinfunction "G_1") (pintype "bidirectional"))
      (node (ref "R44") (pin "2") (pinfunction "2_2") (pintype "passive"))
      (node (ref "R73") (pin "1") (pinfunction "1_1") (pintype "passive"))
    )
    (net (code "67") (name "Net-(Q11-B)") (class "Default")
      (node (ref "Q11") (pin "2") (pinfunction "B_2") (pintype "passive"))
      (node (ref "R6") (pin "1") (pinfunction "1_1") (pintype "passive"))
      (node (ref "R7") (pin "1") (pinfunction "1_1") (pintype "passive"))
    )
    (net (code "68") (name "Net-(U$1-3V3)") (class "Default")
      (node (ref "SJ1") (pin "2") (pinfunction "2_2") (pintype "passive"))
      (node (ref "U$1") (pin "1") (pinfunction "3V3_1") (pintype "bidirectional"))
    )
    (net (code "69") (name "Net-(X19A-SK)") (class "Default")
      (node (ref "J1") (pin "NC") (pinfunction "NC_NC") (pintype "bidirectional"))
      (node (ref "X19") (pin "1") (pinfunction "SK_1") (pintype "passive"))
    )
    (net (code "70") (name "Net-(X19B-SK)") (class "Default")
      (node (ref "J1") (pin "C1") (pinfunction "C_C1") (pintype "bidirectional"))
      (node (ref "J1") (pin "C2") (pinfunction "C_C2") (pintype "bidirectional"))
      (node (ref "X19") (pin "2") (pinfunction "SK_2") (pintype "passive"))
    )
    (net (code "71") (name "Net-(X19C-SK)") (class "Default")
      (node (ref "J1") (pin "NO") (pinfunction "NO_NO") (pintype "bidirectional"))
      (node (ref "X19") (pin "3") (pinfunction "SK_3") (pintype "passive"))
    )
    (net (code "72") (name "OUT1") (class "Default")
      (node (ref "R44") (pin "1") (pinfunction "1_1") (pintype "passive"))
      (node (ref "U$1") (pin "27") (pinfunction "IO16_27") (pintype "bidirectional"))
    )
    (net (code "73") (name "OUT2") (class "Default")
      (node (ref "R45") (pin "1") (pinfunction "1_1") (pintype "passive"))
      (node (ref "U$1") (pin "28") (pinfunction "IO17_28") (pintype "bidirectional"))
    )
    (net (code "74") (name "OUT3") (class "Default")
      (node (ref "R46") (pin "1") (pinfunction "1_1") (pintype "passive"))
      (node (ref "U$1") (pin "30") (pinfunction "IO18_30") (pintype "bidirectional"))
    )
    (net (code "75") (name "OUT4") (class "Default")
      (node (ref "R47") (pin "1") (pinfunction "1_1") (pintype "passive"))
      (node (ref "U$1") (pin "31") (pinfunction "IO19_31") (pintype "bidirectional"))
    )
    (net (code "76") (name "OUT5") (class "Default")
      (node (ref "R51") (pin "1") (pinfunction "1_1") (pintype "passive"))
      (node (ref "U$1") (pin "33") (pinfunction "IO21_33") (pintype "bidirectional"))
    )
    (net (code "77") (name "OUT6") (class "Default")
      (node (ref "R52") (pin "1") (pinfunction "1_1") (pintype "passive"))
      (node (ref "U$1") (pin "36") (pinfunction "IO22_36") (pintype "bidirectional"))
    )
    (net (code "78") (name "OUT7") (class "Default")
      (node (ref "R54") (pin "1") (pinfunction "1_1") (pintype "passive"))
      (node (ref "U$1") (pin "37") (pinfunction "IO23_37") (pintype "bidirectional"))
    )
    (net (code "79") (name "OUT8") (class "Default")
      (node (ref "R55") (pin "1") (pinfunction "1_1") (pintype "passive"))
      (node (ref "U$1") (pin "9") (pinfunction "IO25_9") (pintype "bidirectional"))
    )
    (net (code "80") (name "VM") (class "Default")
      (node (ref "C12") (pin "+") (pinfunction "+_+") (pintype "passive"))
      (node (ref "C35") (pin "A") (pinfunction "+_A") (pintype "passive"))
      (node (ref "IC1") (pin "3") (pinfunction "V+_3") (pintype "power_in"))
      (node (ref "IC2") (pin "3") (pinfunction "V+_3") (pintype "power_in"))
      (node (ref "IC3") (pin "3") (pinfunction "V+_3") (pintype "power_in"))
      (node (ref "IC4") (pin "3") (pinfunction "V+_3") (pintype "power_in"))
      (node (ref "IC5") (pin "1") (pinfunction "IN_1") (pintype "bidirectional"))
      (node (ref "R10") (pin "2") (pinfunction "2_2") (pintype "passive"))
      (node (ref "R11") (pin "2") (pinfunction "2_2") (pintype "passive"))
      (node (ref "R18") (pin "2") (pinfunction "2_2") (pintype "passive"))
      (node (ref "R19") (pin "2") (pinfunction "2_2") (pintype "passive"))
      (node (ref "R2") (pin "2") (pinfunction "2_2") (pintype "passive"))
      (node (ref "R3") (pin "2") (pinfunction "2_2") (pintype "passive"))
      (node (ref "R32") (pin "2") (pinfunction "2_2") (pintype "passive"))
      (node (ref "R33") (pin "2") (pinfunction "2_2") (pintype "passive"))
      (node (ref "R40") (pin "2") (pinfunction "2_2") (pintype "passive"))
      (node (ref "R41") (pin "2") (pinfunction "2_2") (pintype "passive"))
      (node (ref "R48") (pin "2") (pinfunction "2_2") (pintype "passive"))
      (node (ref "R49") (pin "2") (pinfunction "2_2") (pintype "passive"))
      (node (ref "R58") (pin "2") (pinfunction "2_2") (pintype "passive"))
      (node (ref "R59") (pin "2") (pinfunction "2_2") (pintype "passive"))
      (node (ref "R68") (pin "2") (pinfunction "2_2") (pintype "passive"))
      (node (ref "R69") (pin "2") (pinfunction "2_2") (pintype "passive"))
      (node (ref "X17") (pin "1") (pinfunction "SK_1") (pintype "passive"))
      (node (ref "X18") (pin "1") (pinfunction "SK_1") (pintype "passive"))
      (node (ref "X2") (pin "2") (pinfunction "SK_2") (pintype "passive"))
      (node (ref "X3") (pin "1") (pinfunction "SK_1") (pintype "passive"))
      (node (ref "X4") (pin "1") (pinfunction "SK_1") (pintype "passive"))
      (node (ref "X5") (pin "1") (pinfunction "SK_1") (pintype "passive"))
      (node (ref "X6") (pin "1") (pinfunction "SK_1") (pintype "passive"))
      (node (ref "X7") (pin "1") (pinfunction "SK_1") (pintype "passive"))
      (node (ref "X8") (pin "1") (pinfunction "SK_1") (pintype "passive"))
    )
    (net (code "81") (name "unconnected-(S1-NC-Pad3)") (class "Default")
      (node (ref "S1") (pin "3") (pinfunction "NC_3") (pintype "bidirectional"))
    )
    (net (code "82") (name "unconnected-(U$1-CLK-Pad20)") (class "Default")
      (node (ref "U$1") (pin "20") (pinfunction "CLK_20") (pintype "bidirectional"))
    )
    (net (code "83") (name "unconnected-(U$1-CMD-Pad18)") (class "Default")
      (node (ref "U$1") (pin "18") (pinfunction "CMD_18") (pintype "bidirectional"))
    )
    (net (code "84") (name "unconnected-(U$1-EN-Pad2)") (class "Default")
      (node (ref "U$1") (pin "2") (pinfunction "EN_2") (pintype "bidirectional"))
    )
    (net (code "85") (name "unconnected-(U$1-GND-Pad32)") (class "Default")
      (node (ref "U$1") (pin "32") (pinfunction "GND_32") (pintype "bidirectional"))
    )
    (net (code "86") (name "unconnected-(U$1-RXD0-Pad34)") (class "Default")
      (node (ref "U$1") (pin "34") (pinfunction "RXD0_34") (pintype "bidirectional"))
    )
    (net (code "87") (name "unconnected-(U$1-SD0-Pad21)") (class "Default")
      (node (ref "U$1") (pin "21") (pinfunction "SD0_21") (pintype "bidirectional"))
    )
    (net (code "88") (name "unconnected-(U$1-SD1-Pad22)") (class "Default")
      (node (ref "U$1") (pin "22") (pinfunction "SD1_22") (pintype "bidirectional"))
    )
    (net (code "89") (name "unconnected-(U$1-SD2-Pad16)") (class "Default")
      (node (ref "U$1") (pin "16") (pinfunction "SD2_16") (pintype "bidirectional"))
    )
    (net (code "90") (name "unconnected-(U$1-SD3-Pad17)") (class "Default")
      (node (ref "U$1") (pin "17") (pinfunction "SD3_17") (pintype "bidirectional"))
    )
    (net (code "91") (name "unconnected-(U$1-TXD0-Pad35)") (class "Default")
      (node (ref "U$1") (pin "35") (pinfunction "TXD0_35") (pintype "bidirectional"))
    )
  )
)
